# USB-PC.net
KiCad netlist of a schematic drawn in Altium Designer
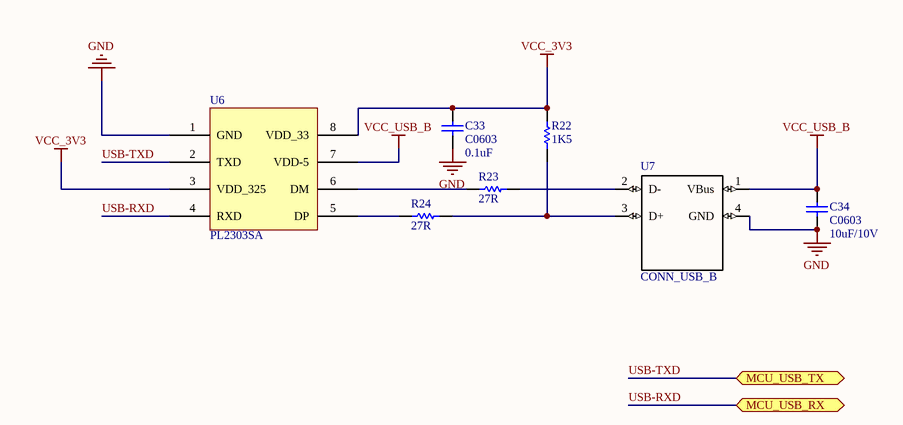
[diagram p0: USB-PC.SchDoc]

(export (version "E")
  (design (tool "Eeschema 10.0.6"))
  (components
    (comp (ref "C33")
      (value "C0603")
      (footprint "C0603")
      (description "Ceramic Chip Capacitor - Standard")
      (fields (field (name "ALTIUM_VALUE") "0.1uF") (field (name "PUBLISHER") "Altium Limited"))
      (libsource (lib "haberlesme") (part "C0603"))
    )
    (comp (ref "C34")
      (value "C0603")
      (footprint "C0603")
      (description "Ceramic Chip Capacitor - Standard")
      (fields (field (name "ALTIUM_VALUE") "10uF/10V") (field (name "PUBLISHER") "Altium Limited"))
      (libsource (lib "haberlesme") (part "C0603"))
    )
    (comp (ref "R22")
      (value "1K5")
      (footprint "Isbak:CC1608-0603")
      (description "Resistor")
      (fields
        (field (name "MANUFACTURER") "Generic Components")
        (field (name "Comment") "Res0603")
        (field (name "PUBLISHER") "Altium Limited")
      )
      (libsource (lib "Isbak") (part "Res0603"))
    )
    (comp (ref "R23")
      (value "27R")
      (footprint "Isbak:CC1608-0603")
      (description "Resistor")
      (fields
        (field (name "MANUFACTURER") "Generic Components")
        (field (name "Comment") "Res0603")
        (field (name "PUBLISHER") "Altium Limited")
      )
      (libsource (lib "Isbak") (part "Res0603"))
    )
    (comp (ref "R24")
      (value "27R")
      (footprint "Isbak:CC1608-0603")
      (description "Resistor")
      (fields
        (field (name "MANUFACTURER") "Generic Components")
        (field (name "Comment") "Res0603")
        (field (name "PUBLISHER") "Altium Limited")
      )
      (libsource (lib "Isbak") (part "Res0603"))
    )
    (comp (ref "U6")
      (value "PL2303SA")
      (footprint "PL2302SA")
      (libsource (lib "haberlesme") (part "PL2303SA"))
    )
    (comp (ref "U7")
      (value "CONN_USB_B")
      (footprint "CONN_USB_B")
      (libsource (lib "haberlesme") (part "CONN_USB_B"))
    )
  )
  (nets
    (net (code "1") (name "/USB-RXD") (class "Default")
      (node (ref "U6") (pin "4") (pinfunction "RXD_4") (pintype "passive"))
    )
    (net (code "2") (name "/USB-TXD") (class "Default")
      (node (ref "U6") (pin "2") (pinfunction "TXD_2") (pintype "passive"))
    )
    (net (code "3") (name "GND") (class "Default")
      (node (ref "C33") (pin "1") (pinfunction "1_1") (pintype "passive"))
      (node (ref "C34") (pin "1") (pinfunction "1_1") (pintype "passive"))
      (node (ref "U6") (pin "1") (pinfunction "GND_1") (pintype "passive"))
      (node (ref "U7") (pin "4") (pinfunction "GND_4") (pintype "bidirectional"))
    )
    (net (code "4") (name "Net-(U6-DM)") (class "Default")
      (node (ref "R23") (pin "2") (pinfunction "2_2") (pintype "passive"))
      (node (ref "U6") (pin "6") (pinfunction "DM_6") (pintype "passive"))
    )
    (net (code "5") (name "Net-(U6-DP)") (class "Default")
      (node (ref "R24") (pin "2") (pinfunction "2_2") (pintype "passive"))
      (node (ref "U6") (pin "5") (pinfunction "DP_5") (pintype "passive"))
    )
    (net (code "6") (name "Net-(U7-D+)") (class "Default")
      (node (ref "R22") (pin "1") (pinfunction "1_1") (pintype "passive"))
      (node (ref "R24") (pin "1") (pinfunction "1_1") (pintype "passive"))
      (node (ref "U7") (pin "3") (pinfunction "D+_3") (pintype "bidirectional"))
    )
    (net (code "7") (name "Net-(U7-D-)") (class "Default")
      (node (ref "R23") (pin "1") (pinfunction "1_1") (pintype "passive"))
      (node (ref "U7") (pin "2") (pinfunction "D-_2") (pintype "bidirectional"))
    )
    (net (code "8") (name "VCC_3V3") (class "Default")
      (node (ref "C33") (pin "2") (pinfunction "2_2") (pintype "passive"))
      (node (ref "R22") (pin "2") (pinfunction "2_2") (pintype "passive"))
      (node (ref "U6") (pin "3") (pinfunction "VDD_325_3") (pintype "passive"))
      (node (ref "U6") (pin "8") (pinfunction "VDD_33_8") (pintype "passive"))
    )
    (net (code "9") (name "VCC_USB_B") (class "Default")
      (node (ref "C34") (pin "2") (pinfunction "2_2") (pintype "passive"))
      (node (ref "U6") (pin "7") (pinfunction "VDD-5_7") (pintype "passive"))
      (node (ref "U7") (pin "1") (pinfunction "VBus_1") (pintype "bidirectional"))
    )
  )
)
